# Actuators_Schematic.net
KiCad netlist of a schematic drawn in Altium Designer
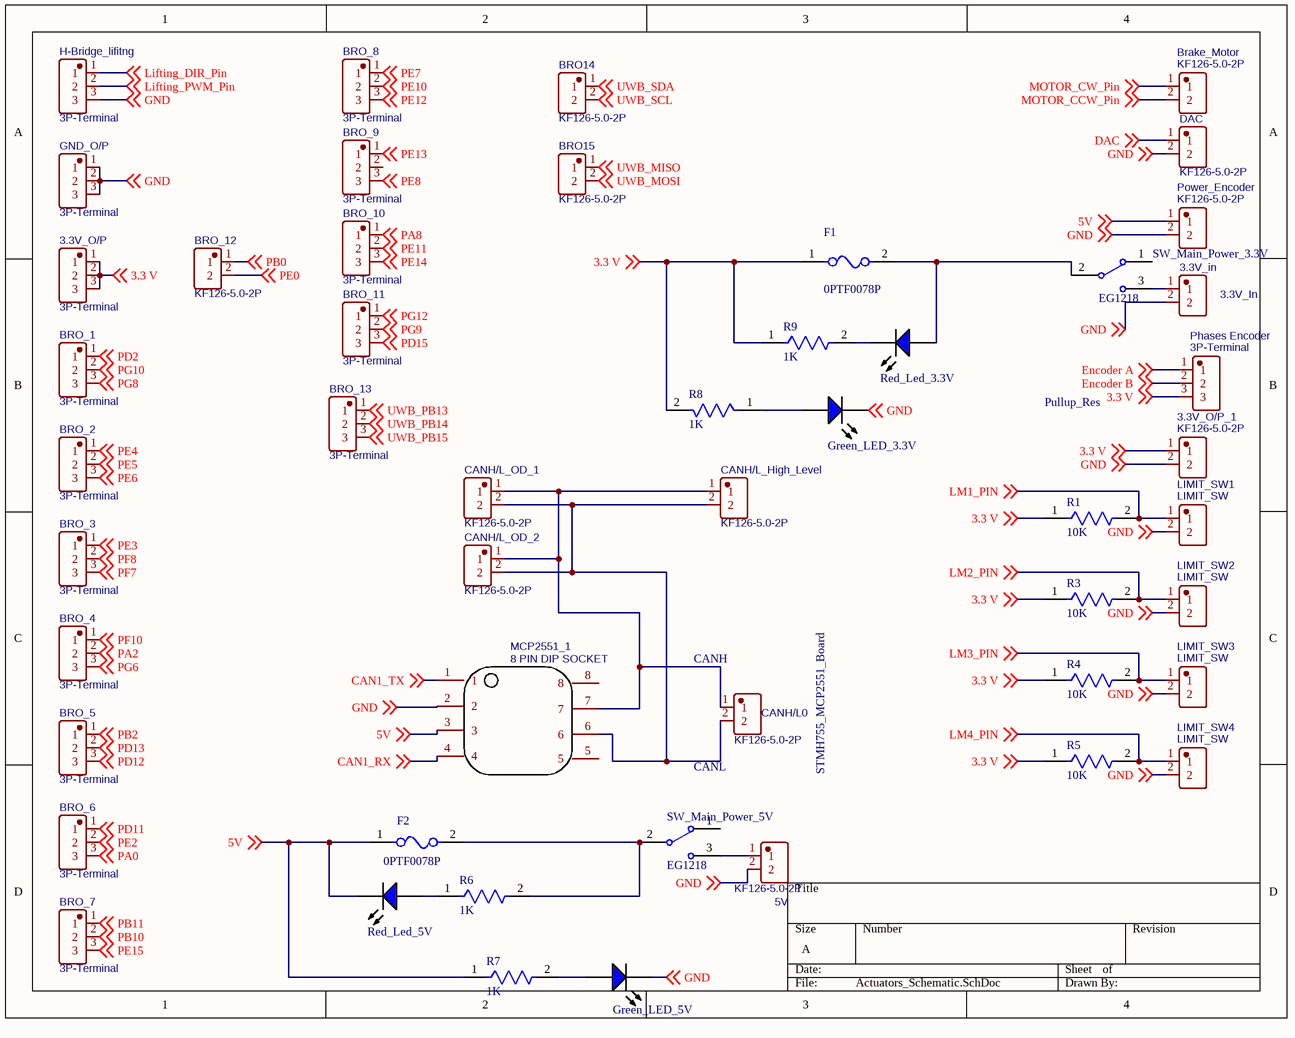
[diagram p0: Actuators_Schematic.SchDoc]

(export (version "E")
  (design (tool "Eeschema 10.0.6"))
  (components
    (comp (ref "3.3V_in")
      (value "3.3V_In")
      (footprint "CONN-TH_P5.00_KF126-5.0-2P")
      (fields
        (field (name "MANUFACTURER") "Cixi Kefa Elec")
        (field (name "MANUFACTURER PART") "KF126-5.0-2P")
        (field (name "CONTRIBUTOR") "LCSC")
      )
      (libsource (lib "altium-import") (part "root_0_KF126-5.0-2P_"))
    )
    (comp (ref "3.3V_O/P")
      (value "3P-Terminal")
      (footprint "CONN-TH_3P-P5.00_KF126-5.0-3P")
      (fields
        (field (name "MANUFACTURER") "Cixi Kefa Elec")
        (field (name "MANUFACTURER PART") "KF126-5.0-3P")
        (field (name "CONTRIBUTOR") "thulasikrishna")
      )
      (libsource (lib "altium-import") (part "root_0_mirrored_Limit Switch_"))
    )
    (comp (ref "3.3V_O/P_1")
      (value "KF126-5.0-2P")
      (footprint "CONN-TH_P5.00_KF126-5.0-2P")
      (fields (field (name "MANUFACTURER") "Cixi Kefa Elec") (field (name "CONTRIBUTOR") "LCSC"))
      (libsource (lib "altium-import") (part "root_0_KF126-5.0-2P_"))
    )
    (comp (ref "5V")
      (value "KF126-5.0-2P")
      (footprint "CONN-TH_P5.00_KF126-5.0-2P")
      (fields (field (name "MANUFACTURER") "Cixi Kefa Elec") (field (name "CONTRIBUTOR") "LCSC"))
      (libsource (lib "altium-import") (part "root_0_KF126-5.0-2P_"))
    )
    (comp (ref "Brake_Motor")
      (value "KF126-5.0-2P")
      (footprint "CONN-TH_P5.00_KF126-5.0-2P")
      (fields (field (name "MANUFACTURER") "Cixi Kefa Elec") (field (name "CONTRIBUTOR") "LCSC"))
      (libsource (lib "altium-import") (part "root_0_KF126-5.0-2P_"))
    )
    (comp (ref "BRO14")
      (value "KF126-5.0-2P")
      (footprint "CONN-TH_P5.00_KF126-5.0-2P")
      (fields (field (name "MANUFACTURER") "Cixi Kefa Elec") (field (name "CONTRIBUTOR") "LCSC"))
      (libsource (lib "altium-import") (part "root_0_mirrored_KF126-5.0-2P_"))
    )
    (comp (ref "BRO15")
      (value "KF126-5.0-2P")
      (footprint "CONN-TH_P5.00_KF126-5.0-2P")
      (fields (field (name "MANUFACTURER") "Cixi Kefa Elec") (field (name "CONTRIBUTOR") "LCSC"))
      (libsource (lib "altium-import") (part "root_0_mirrored_KF126-5.0-2P_"))
    )
    (comp (ref "BRO_1")
      (value "3P-Terminal")
      (footprint "CONN-TH_3P-P5.00_KF126-5.0-3P")
      (fields
        (field (name "MANUFACTURER") "Cixi Kefa Elec")
        (field (name "MANUFACTURER PART") "KF126-5.0-3P")
        (field (name "CONTRIBUTOR") "thulasikrishna")
      )
      (libsource (lib "altium-import") (part "root_0_mirrored_Limit Switch_"))
    )
    (comp (ref "BRO_2")
      (value "3P-Terminal")
      (footprint "CONN-TH_3P-P5.00_KF126-5.0-3P")
      (fields
        (field (name "MANUFACTURER") "Cixi Kefa Elec")
        (field (name "MANUFACTURER PART") "KF126-5.0-3P")
        (field (name "CONTRIBUTOR") "thulasikrishna")
      )
      (libsource (lib "altium-import") (part "root_0_mirrored_Limit Switch_"))
    )
    (comp (ref "BRO_3")
      (value "3P-Terminal")
      (footprint "CONN-TH_3P-P5.00_KF126-5.0-3P")
      (fields
        (field (name "MANUFACTURER") "Cixi Kefa Elec")
        (field (name "MANUFACTURER PART") "KF126-5.0-3P")
        (field (name "CONTRIBUTOR") "thulasikrishna")
      )
      (libsource (lib "altium-import") (part "root_0_mirrored_Limit Switch_"))
    )
    (comp (ref "BRO_4")
      (value "3P-Terminal")
      (footprint "CONN-TH_3P-P5.00_KF126-5.0-3P")
      (fields
        (field (name "MANUFACTURER") "Cixi Kefa Elec")
        (field (name "MANUFACTURER PART") "KF126-5.0-3P")
        (field (name "CONTRIBUTOR") "thulasikrishna")
      )
      (libsource (lib "altium-import") (part "root_0_mirrored_Limit Switch_"))
    )
    (comp (ref "BRO_5")
      (value "3P-Terminal")
      (footprint "CONN-TH_3P-P5.00_KF126-5.0-3P")
      (fields
        (field (name "MANUFACTURER") "Cixi Kefa Elec")
        (field (name "MANUFACTURER PART") "KF126-5.0-3P")
        (field (name "CONTRIBUTOR") "thulasikrishna")
      )
      (libsource (lib "altium-import") (part "root_0_mirrored_Limit Switch_"))
    )
    (comp (ref "BRO_6")
      (value "3P-Terminal")
      (footprint "CONN-TH_3P-P5.00_KF126-5.0-3P")
      (fields
        (field (name "MANUFACTURER") "Cixi Kefa Elec")
        (field (name "MANUFACTURER PART") "KF126-5.0-3P")
        (field (name "CONTRIBUTOR") "thulasikrishna")
      )
      (libsource (lib "altium-import") (part "root_0_mirrored_Limit Switch_"))
    )
    (comp (ref "BRO_7")
      (value "3P-Terminal")
      (footprint "CONN-TH_3P-P5.00_KF126-5.0-3P")
      (fields
        (field (name "MANUFACTURER") "Cixi Kefa Elec")
        (field (name "MANUFACTURER PART") "KF126-5.0-3P")
        (field (name "CONTRIBUTOR") "thulasikrishna")
      )
      (libsource (lib "altium-import") (part "root_0_mirrored_Limit Switch_"))
    )
    (comp (ref "BRO_8")
      (value "3P-Terminal")
      (footprint "CONN-TH_3P-P5.00_KF126-5.0-3P")
      (fields
        (field (name "MANUFACTURER") "Cixi Kefa Elec")
        (field (name "MANUFACTURER PART") "KF126-5.0-3P")
        (field (name "CONTRIBUTOR") "thulasikrishna")
      )
      (libsource (lib "altium-import") (part "root_0_mirrored_Limit Switch_"))
    )
    (comp (ref "BRO_9")
      (value "3P-Terminal")
      (footprint "CONN-TH_3P-P5.00_KF126-5.0-3P")
      (fields
        (field (name "MANUFACTURER") "Cixi Kefa Elec")
        (field (name "MANUFACTURER PART") "KF126-5.0-3P")
        (field (name "CONTRIBUTOR") "thulasikrishna")
      )
      (libsource (lib "altium-import") (part "root_0_mirrored_Limit Switch_"))
    )
    (comp (ref "BRO_10")
      (value "3P-Terminal")
      (footprint "CONN-TH_3P-P5.00_KF126-5.0-3P")
      (fields
        (field (name "MANUFACTURER") "Cixi Kefa Elec")
        (field (name "MANUFACTURER PART") "KF126-5.0-3P")
        (field (name "CONTRIBUTOR") "thulasikrishna")
      )
      (libsource (lib "altium-import") (part "root_0_mirrored_Limit Switch_"))
    )
    (comp (ref "BRO_11")
      (value "3P-Terminal")
      (footprint "CONN-TH_3P-P5.00_KF126-5.0-3P")
      (fields
        (field (name "MANUFACTURER") "Cixi Kefa Elec")
        (field (name "MANUFACTURER PART") "KF126-5.0-3P")
        (field (name "CONTRIBUTOR") "thulasikrishna")
      )
      (libsource (lib "altium-import") (part "root_0_mirrored_Limit Switch_"))
    )
    (comp (ref "BRO_12")
      (value "KF126-5.0-2P")
      (footprint "CONN-TH_P5.00_KF126-5.0-2P")
      (fields (field (name "MANUFACTURER") "Cixi Kefa Elec") (field (name "CONTRIBUTOR") "LCSC"))
      (libsource (lib "altium-import") (part "root_0_mirrored_KF126-5.0-2P_"))
    )
    (comp (ref "BRO_13")
      (value "3P-Terminal")
      (footprint "CONN-TH_3P-P5.00_KF126-5.0-3P")
      (fields
        (field (name "MANUFACTURER") "Cixi Kefa Elec")
        (field (name "MANUFACTURER PART") "KF126-5.0-3P")
        (field (name "CONTRIBUTOR") "thulasikrishna")
      )
      (libsource (lib "altium-import") (part "root_0_mirrored_Limit Switch_"))
    )
    (comp (ref "CANH/L0")
      (value "KF126-5.0-2P")
      (footprint "CONN-TH_P5.00_KF126-5.0-2P")
      (fields (field (name "MANUFACTURER") "Cixi Kefa Elec") (field (name "CONTRIBUTOR") "LCSC"))
      (libsource (lib "altium-import") (part "root_0_KF126-5.0-2P_"))
    )
    (comp (ref "CANH/L_High_Level")
      (value "KF126-5.0-2P")
      (footprint "CONN-TH_P5.00_KF126-5.0-2P")
      (fields (field (name "MANUFACTURER") "Cixi Kefa Elec") (field (name "CONTRIBUTOR") "LCSC"))
      (libsource (lib "altium-import") (part "root_0_KF126-5.0-2P_"))
    )
    (comp (ref "CANH/L_OD_1")
      (value "KF126-5.0-2P")
      (footprint "CONN-TH_P5.00_KF126-5.0-2P")
      (fields (field (name "MANUFACTURER") "Cixi Kefa Elec") (field (name "CONTRIBUTOR") "LCSC"))
      (libsource (lib "altium-import") (part "root_0_mirrored_KF126-5.0-2P_"))
    )
    (comp (ref "CANH/L_OD_2")
      (value "KF126-5.0-2P")
      (footprint "CONN-TH_P5.00_KF126-5.0-2P")
      (fields (field (name "MANUFACTURER") "Cixi Kefa Elec") (field (name "CONTRIBUTOR") "LCSC"))
      (libsource (lib "altium-import") (part "root_0_mirrored_KF126-5.0-2P_"))
    )
    (comp (ref "DAC")
      (value "KF126-5.0-2P")
      (footprint "CONN-TH_P5.00_KF126-5.0-2P")
      (fields (field (name "MANUFACTURER") "Cixi Kefa Elec") (field (name "CONTRIBUTOR") "LCSC"))
      (libsource (lib "altium-import") (part "root_0_KF126-5.0-2P_"))
    )
    (comp (ref "F1")
      (value "0PTF0078P")
      (footprint "FP-0PTF0078P-MFG")
      (description "FUSE BLOCK CARTRIDGE PCB")
      (fields
        (field (name "OCTOPART") "https://octopart.com/0ptf0078p-littelfuse-13255855")
        (field (name "MANUFACTURER") "Littelfuse Inc")
      )
      (libsource (lib "Altium Content Vault") (part "5bcf9b9f640e542cf0359d10258e979"))
    )
    (comp (ref "F2")
      (value "0PTF0078P")
      (footprint "FP-0PTF0078P-MFG")
      (description "FUSE BLOCK CARTRIDGE PCB")
      (fields
        (field (name "OCTOPART") "https://octopart.com/0ptf0078p-littelfuse-13255855")
        (field (name "MANUFACTURER") "Littelfuse Inc")
      )
      (libsource (lib "Altium Content Vault") (part "5bcf9b9f640e542cf0359d10258e979"))
    )
    (comp (ref "GND_O/P")
      (value "3P-Terminal")
      (footprint "CONN-TH_3P-P5.00_KF126-5.0-3P")
      (fields
        (field (name "MANUFACTURER") "Cixi Kefa Elec")
        (field (name "MANUFACTURER PART") "KF126-5.0-3P")
        (field (name "CONTRIBUTOR") "thulasikrishna")
      )
      (libsource (lib "altium-import") (part "root_0_mirrored_Limit Switch_"))
    )
    (comp (ref "Green_LED_3.3V")
      (value "WP710A10QBC/D")
      (footprint "KING-WP710A10QBCD_V")
      (description "Blue LED, 3.3 V, 20 mA, -40 to 85 degC, 2-Pin THD, RoHS, Bulk")
      (fields (field (name "MANUFACTURER") "Kingbright"))
      (libsource (lib "Altium Content Vault") (part "LED-BLUE-AK-2"))
    )
    (comp (ref "Green_LED_5V")
      (value "WP710A10QBC/D")
      (footprint "KING-WP710A10QBCD_V")
      (description "Blue LED, 3.3 V, 20 mA, -40 to 85 degC, 2-Pin THD, RoHS, Bulk")
      (fields (field (name "MANUFACTURER") "Kingbright"))
      (libsource (lib "Altium Content Vault") (part "LED-BLUE-AK-2"))
    )
    (comp (ref "H-Bridge_lifitng")
      (value "3P-Terminal")
      (footprint "CONN-TH_3P-P5.00_KF126-5.0-3P")
      (fields
        (field (name "MANUFACTURER") "Cixi Kefa Elec")
        (field (name "MANUFACTURER PART") "KF126-5.0-3P")
        (field (name "CONTRIBUTOR") "thulasikrishna")
      )
      (libsource (lib "altium-import") (part "root_0_mirrored_Limit Switch_"))
    )
    (comp (ref "LIMIT_SW1")
      (value "LIMIT_SW")
      (footprint "CONN-TH_P5.00_KF126-5.0-2P")
      (fields
        (field (name "MANUFACTURER") "Cixi Kefa Elec")
        (field (name "MANUFACTURER PART") "KF126-5.0-2P")
        (field (name "CONTRIBUTOR") "LCSC")
      )
      (libsource (lib "altium-import") (part "root_0_KF126-5.0-2P_"))
    )
    (comp (ref "LIMIT_SW2")
      (value "LIMIT_SW")
      (footprint "CONN-TH_P5.00_KF126-5.0-2P")
      (fields
        (field (name "MANUFACTURER") "Cixi Kefa Elec")
        (field (name "MANUFACTURER PART") "KF126-5.0-2P")
        (field (name "CONTRIBUTOR") "LCSC")
      )
      (libsource (lib "altium-import") (part "root_0_KF126-5.0-2P_"))
    )
    (comp (ref "LIMIT_SW3")
      (value "LIMIT_SW")
      (footprint "CONN-TH_P5.00_KF126-5.0-2P")
      (fields
        (field (name "MANUFACTURER") "Cixi Kefa Elec")
        (field (name "MANUFACTURER PART") "KF126-5.0-2P")
        (field (name "CONTRIBUTOR") "LCSC")
      )
      (libsource (lib "altium-import") (part "root_0_KF126-5.0-2P_"))
    )
    (comp (ref "LIMIT_SW4")
      (value "LIMIT_SW")
      (footprint "CONN-TH_P5.00_KF126-5.0-2P")
      (fields
        (field (name "MANUFACTURER") "Cixi Kefa Elec")
        (field (name "MANUFACTURER PART") "KF126-5.0-2P")
        (field (name "CONTRIBUTOR") "LCSC")
      )
      (libsource (lib "altium-import") (part "root_0_KF126-5.0-2P_"))
    )
    (comp (ref "MCP2551_1")
      (value "8 PIN DIP SOCKET")
      (footprint "DIP 8 PIN SOCKET")
      (fields (field (name "CONTRIBUTOR") "uniqengineeringworks"))
      (libsource (lib "altium-import") (part "root_0_8 PIN DIP SOCKET_"))
    )
    (comp (ref "Phases Encoder")
      (value "3P-Terminal")
      (footprint "CONN-TH_3P-P5.00_KF126-5.0-3P")
      (fields
        (field (name "MANUFACTURER") "Cixi Kefa Elec")
        (field (name "MANUFACTURER PART") "KF126-5.0-3P")
        (field (name "CONTRIBUTOR") "thulasikrishna")
      )
      (libsource (lib "altium-import") (part "root_0_Limit Switch_"))
    )
    (comp (ref "Power_Encoder")
      (value "KF126-5.0-2P")
      (footprint "CONN-TH_P5.00_KF126-5.0-2P")
      (fields (field (name "MANUFACTURER") "Cixi Kefa Elec") (field (name "CONTRIBUTOR") "LCSC"))
      (libsource (lib "altium-import") (part "root_0_KF126-5.0-2P_"))
    )
    (comp (ref "R1")
      (value "10K")
      (footprint "FP-MFR-12-MFG")
      (description "RES MF 1/6W 1% AXIAL")
      (fields (field (name "TOLERANCE") "1%"))
      (libsource (lib "Altium Content Vault") (part "1029c3af85768c4190bb7ad29bc67b5"))
    )
    (comp (ref "R3")
      (value "10K")
      (footprint "FP-MFR-12-MFG")
      (description "RES MF 1/6W 1% AXIAL")
      (fields (field (name "TOLERANCE") "1%"))
      (libsource (lib "Altium Content Vault") (part "1029c3af85768c4190bb7ad29bc67b5"))
    )
    (comp (ref "R4")
      (value "10K")
      (footprint "FP-MFR-12-MFG")
      (description "RES MF 1/6W 1% AXIAL")
      (fields (field (name "TOLERANCE") "1%"))
      (libsource (lib "Altium Content Vault") (part "1029c3af85768c4190bb7ad29bc67b5"))
    )
    (comp (ref "R5")
      (value "10K")
      (footprint "FP-MFR-12-MFG")
      (description "RES MF 1/6W 1% AXIAL")
      (fields (field (name "TOLERANCE") "1%"))
      (libsource (lib "Altium Content Vault") (part "1029c3af85768c4190bb7ad29bc67b5"))
    )
    (comp (ref "R6")
      (value "1K")
      (footprint "FP-MFR-12-MFG")
      (description "RES MF 1/6W 1% AXIAL")
      (fields (field (name "TOLERANCE") "1%"))
      (libsource (lib "Altium Content Vault") (part "1029c3af85768c4190bb7ad29bc67b5"))
    )
    (comp (ref "R7")
      (value "1K")
      (footprint "FP-MFR-12-MFG")
      (description "RES MF 1/6W 1% AXIAL")
      (fields (field (name "TOLERANCE") "1%"))
      (libsource (lib "Altium Content Vault") (part "1029c3af85768c4190bb7ad29bc67b5"))
    )
    (comp (ref "R8")
      (value "1K")
      (footprint "FP-MFR-12-MFG")
      (description "RES MF 1/6W 1% AXIAL")
      (fields (field (name "TOLERANCE") "1%"))
      (libsource (lib "Altium Content Vault") (part "1029c3af85768c4190bb7ad29bc67b5"))
    )
    (comp (ref "R9")
      (value "1K")
      (footprint "FP-MFR-12-MFG")
      (description "RES MF 1/6W 1% AXIAL")
      (fields (field (name "TOLERANCE") "1%"))
      (libsource (lib "Altium Content Vault") (part "1029c3af85768c4190bb7ad29bc67b5"))
    )
    (comp (ref "Red_Led_3.3V")
      (value "WP710A10QBC/D")
      (footprint "KING-WP710A10QBCD_V")
      (description "Blue LED, 3.3 V, 20 mA, -40 to 85 degC, 2-Pin THD, RoHS, Bulk")
      (fields (field (name "MANUFACTURER") "Kingbright"))
      (libsource (lib "Altium Content Vault") (part "LED-BLUE-AK-2"))
    )
    (comp (ref "Red_Led_5V")
      (value "WP710A10QBC/D")
      (footprint "KING-WP710A10QBCD_V")
      (description "Blue LED, 3.3 V, 20 mA, -40 to 85 degC, 2-Pin THD, RoHS, Bulk")
      (fields (field (name "MANUFACTURER") "Kingbright"))
      (libsource (lib "Altium Content Vault") (part "LED-BLUE-AK-2"))
    )
    (comp (ref "SW_Main_Power_3.3V")
      (value "EG1218")
      (footprint "ESWI-EG1218_V")
      (description "Slide Switch, 500 V, -20 to 70 degC, 3-Pin THD, RoHS")
      (libsource (lib "Altium Content Vault") (part "SW-SPDT-3_B"))
    )
    (comp (ref "SW_Main_Power_5V")
      (value "EG1218")
      (footprint "ESWI-EG1218_V")
      (description "Slide Switch, 500 V, -20 to 70 degC, 3-Pin THD, RoHS")
      (libsource (lib "Altium Content Vault") (part "SW-SPDT-3_B"))
    )
  )
  (nets
    (net (code "1") (name "3.3 V") (class "Default")
      (node (ref "3.3V_O/P") (pin "1") (pinfunction "1_1") (pintype "passive"))
      (node (ref "3.3V_O/P") (pin "2") (pinfunction "2_2") (pintype "passive"))
      (node (ref "3.3V_O/P") (pin "3") (pinfunction "3_3") (pintype "passive"))
      (node (ref "3.3V_O/P_1") (pin "1") (pinfunction "1_1") (pintype "passive"))
      (node (ref "F1") (pin "1") (pinfunction "1_1") (pintype "passive"))
      (node (ref "Phases Encoder") (pin "3") (pinfunction "3_3") (pintype "passive"))
      (node (ref "R1") (pin "1") (pinfunction "1_1") (pintype "passive"))
      (node (ref "R3") (pin "1") (pinfunction "1_1") (pintype "passive"))
      (node (ref "R4") (pin "1") (pinfunction "1_1") (pintype "passive"))
      (node (ref "R5") (pin "1") (pinfunction "1_1") (pintype "passive"))
      (node (ref "R8") (pin "2") (pinfunction "2_2") (pintype "passive"))
      (node (ref "R9") (pin "1") (pinfunction "1_1") (pintype "passive"))
    )
    (net (code "2") (name "5V") (class "Default")
      (node (ref "F2") (pin "1") (pinfunction "1_1") (pintype "passive"))
      (node (ref "MCP2551_1") (pin "3") (pinfunction "3_3") (pintype "passive"))
      (node (ref "Power_Encoder") (pin "1") (pinfunction "1_1") (pintype "passive"))
      (node (ref "R7") (pin "1") (pinfunction "1_1") (pintype "passive"))
      (node (ref "Red_Led_5V") (pin "2") (pinfunction "K_2") (pintype "passive"))
    )
    (net (code "3") (name "CAN1_RX") (class "Default")
      (node (ref "MCP2551_1") (pin "4") (pinfunction "4_4") (pintype "passive"))
    )
    (net (code "4") (name "CAN1_TX") (class "Default")
      (node (ref "MCP2551_1") (pin "1") (pinfunction "1_1") (pintype "passive"))
    )
    (net (code "5") (name "DAC") (class "Default")
      (node (ref "DAC") (pin "1") (pinfunction "1_1") (pintype "passive"))
    )
    (net (code "6") (name "Encoder A") (class "Default")
      (node (ref "Phases Encoder") (pin "1") (pinfunction "1_1") (pintype "passive"))
    )
    (net (code "7") (name "Encoder B") (class "Default")
      (node (ref "Phases Encoder") (pin "2") (pinfunction "2_2") (pintype "passive"))
    )
    (net (code "8") (name "GND") (class "Default")
      (node (ref "3.3V_O/P_1") (pin "2") (pinfunction "2_2") (pintype "passive"))
      (node (ref "3.3V_in") (pin "2") (pinfunction "2_2") (pintype "passive"))
      (node (ref "5V") (pin "2") (pinfunction "2_2") (pintype "passive"))
      (node (ref "DAC") (pin "2") (pinfunction "2_2") (pintype "passive"))
      (node (ref "GND_O/P") (pin "1") (pinfunction "1_1") (pintype "passive"))
      (node (ref "GND_O/P") (pin "2") (pinfunction "2_2") (pintype "passive"))
      (node (ref "GND_O/P") (pin "3") (pinfunction "3_3") (pintype "passive"))
      (node (ref "Green_LED_3.3V") (pin "2") (pinfunction "K_2") (pintype "passive"))
      (node (ref "Green_LED_5V") (pin "2") (pinfunction "K_2") (pintype "passive"))
      (node (ref "H-Bridge_lifitng") (pin "3") (pinfunction "3_3") (pintype "passive"))
      (node (ref "LIMIT_SW1") (pin "2") (pinfunction "2_2") (pintype "passive"))
      (node (ref "LIMIT_SW2") (pin "2") (pinfunction "2_2") (pintype "passive"))
      (node (ref "LIMIT_SW3") (pin "2") (pinfunction "2_2") (pintype "passive"))
      (node (ref "LIMIT_SW4") (pin "2") (pinfunction "2_2") (pintype "passive"))
      (node (ref "MCP2551_1") (pin "2") (pinfunction "2_2") (pintype "passive"))
      (node (ref "Power_Encoder") (pin "2") (pinfunction "2_2") (pintype "passive"))
    )
    (net (code "9") (name "LM1_PIN") (class "Default")
      (node (ref "LIMIT_SW1") (pin "1") (pinfunction "1_1") (pintype "passive"))
      (node (ref "R1") (pin "2") (pinfunction "2_2") (pintype "passive"))
    )
    (net (code "10") (name "LM2_PIN") (class "Default")
      (node (ref "LIMIT_SW2") (pin "1") (pinfunction "1_1") (pintype "passive"))
      (node (ref "R3") (pin "2") (pinfunction "2_2") (pintype "passive"))
    )
    (net (code "11") (name "LM3_PIN") (class "Default")
      (node (ref "LIMIT_SW3") (pin "1") (pinfunction "1_1") (pintype "passive"))
      (node (ref "R4") (pin "2") (pinfunction "2_2") (pintype "passive"))
    )
    (net (code "12") (name "LM4_PIN") (class "Default")
      (node (ref "LIMIT_SW4") (pin "1") (pinfunction "1_1") (pintype "passive"))
      (node (ref "R5") (pin "2") (pinfunction "2_2") (pintype "passive"))
    )
    (net (code "13") (name "Lifting_DIR_Pin") (class "Default")
      (node (ref "H-Bridge_lifitng") (pin "1") (pinfunction "1_1") (pintype "passive"))
    )
    (net (code "14") (name "Lifting_PWM_Pin") (class "Default")
      (node (ref "H-Bridge_lifitng") (pin "2") (pinfunction "2_2") (pintype "passive"))
    )
    (net (code "15") (name "MOTOR_CCW_Pin") (class "Default")
      (node (ref "Brake_Motor") (pin "2") (pinfunction "2_2") (pintype "passive"))
    )
    (net (code "16") (name "MOTOR_CW_Pin") (class "Default")
      (node (ref "Brake_Motor") (pin "1") (pinfunction "1_1") (pintype "passive"))
    )
    (net (code "17") (name "Net-(3.3V_in-Pad1)") (class "Default")
      (node (ref "3.3V_in") (pin "1") (pinfunction "1_1") (pintype "passive"))
      (node (ref "SW_Main_Power_3.3V") (pin "3") (pinfunction "3_3") (pintype "passive"))
    )
    (net (code "18") (name "Net-(5V-Pad1)") (class "Default")
      (node (ref "5V") (pin "1") (pinfunction "1_1") (pintype "passive"))
      (node (ref "SW_Main_Power_5V") (pin "3") (pinfunction "3_3") (pintype "passive"))
    )
    (net (code "19") (name "Net-(CANH/L0-Pad1)") (class "Default")
      (node (ref "CANH/L0") (pin "1") (pinfunction "1_1") (pintype "passive"))
      (node (ref "CANH/L_High_Level") (pin "1") (pinfunction "1_1") (pintype "passive"))
      (node (ref "CANH/L_OD_1") (pin "1") (pinfunction "1_1") (pintype "passive"))
      (node (ref "CANH/L_OD_2") (pin "1") (pinfunction "1_1") (pintype "passive"))
      (node (ref "MCP2551_1") (pin "7") (pinfunction "7_7") (pintype "passive"))
    )
    (net (code "20") (name "Net-(CANH/L0-Pad2)") (class "Default")
      (node (ref "CANH/L0") (pin "2") (pinfunction "2_2") (pintype "passive"))
      (node (ref "CANH/L_High_Level") (pin "2") (pinfunction "2_2") (pintype "passive"))
      (node (ref "CANH/L_OD_1") (pin "2") (pinfunction "2_2") (pintype "passive"))
      (node (ref "CANH/L_OD_2") (pin "2") (pinfunction "2_2") (pintype "passive"))
      (node (ref "MCP2551_1") (pin "6") (pinfunction "6_6") (pintype "passive"))
    )
    (net (code "21") (name "Net-(Green_LED_3.3V-A)") (class "Default")
      (node (ref "Green_LED_3.3V") (pin "1") (pinfunction "A_1") (pintype "passive"))
      (node (ref "R8") (pin "1") (pinfunction "1_1") (pintype "passive"))
    )
    (net (code "22") (name "Net-(Green_LED_5V-A)") (class "Default")
      (node (ref "Green_LED_5V") (pin "1") (pinfunction "A_1") (pintype "passive"))
      (node (ref "R7") (pin "2") (pinfunction "2_2") (pintype "passive"))
    )
    (net (code "23") (name "Net-(Red_Led_3.3V-A)") (class "Default")
      (node (ref "F1") (pin "2") (pinfunction "2_2") (pintype "passive"))
      (node (ref "Red_Led_3.3V") (pin "1") (pinfunction "A_1") (pintype "passive"))
      (node (ref "SW_Main_Power_3.3V") (pin "2") (pinfunction "COM_2") (pintype "passive"))
    )
    (net (code "24") (name "Net-(Red_Led_3.3V-K)") (class "Default")
      (node (ref "R9") (pin "2") (pinfunction "2_2") (pintype "passive"))
      (node (ref "Red_Led_3.3V") (pin "2") (pinfunction "K_2") (pintype "passive"))
    )
    (net (code "25") (name "Net-(Red_Led_5V-A)") (class "Default")
      (node (ref "R6") (pin "1") (pinfunction "1_1") (pintype "passive"))
      (node (ref "Red_Led_5V") (pin "1") (pinfunction "A_1") (pintype "passive"))
    )
    (net (code "26") (name "Net-(SW_Main_Power_5V-COM)") (class "Default")
      (node (ref "F2") (pin "2") (pinfunction "2_2") (pintype "passive"))
      (node (ref "R6") (pin "2") (pinfunction "2_2") (pintype "passive"))
      (node (ref "SW_Main_Power_5V") (pin "2") (pinfunction "COM_2") (pintype "passive"))
    )
    (net (code "27") (name "PA0") (class "Default")
      (node (ref "BRO_6") (pin "3") (pinfunction "3_3") (pintype "passive"))
    )
    (net (code "28") (name "PA2") (class "Default")
      (node (ref "BRO_4") (pin "2") (pinfunction "2_2") (pintype "passive"))
    )
    (net (code "29") (name "PA8") (class "Default")
      (node (ref "BRO_10") (pin "1") (pinfunction "1_1") (pintype "passive"))
    )
    (net (code "30") (name "PB0") (class "Default")
      (node (ref "BRO_12") (pin "1") (pinfunction "1_1") (pintype "passive"))
    )
    (net (code "31") (name "PB2") (class "Default")
      (node (ref "BRO_5") (pin "1") (pinfunction "1_1") (pintype "passive"))
    )
    (net (code "32") (name "PB10") (class "Default")
      (node (ref "BRO_7") (pin "2") (pinfunction "2_2") (pintype "passive"))
    )
    (net (code "33") (name "PB11") (class "Default")
      (node (ref "BRO_7") (pin "1") (pinfunction "1_1") (pintype "passive"))
    )
    (net (code "34") (name "PD2") (class "Default")
      (node (ref "BRO_1") (pin "1") (pinfunction "1_1") (pintype "passive"))
    )
    (net (code "35") (name "PD11") (class "Default")
      (node (ref "BRO_6") (pin "1") (pinfunction "1_1") (pintype "passive"))
    )
    (net (code "36") (name "PD12") (class "Default")
      (node (ref "BRO_5") (pin "3") (pinfunction "3_3") (pintype "passive"))
    )
    (net (code "37") (name "PD13") (class "Default")
      (node (ref "BRO_5") (pin "2") (pinfunction "2_2") (pintype "passive"))
    )
    (net (code "38") (name "PD15") (class "Default")
      (node (ref "BRO_11") (pin "3") (pinfunction "3_3") (pintype "passive"))
    )
    (net (code "39") (name "PE0") (class "Default")
      (node (ref "BRO_12") (pin "2") (pinfunction "2_2") (pintype "passive"))
    )
    (net (code "40") (name "PE2") (class "Default")
      (node (ref "BRO_6") (pin "2") (pinfunction "2_2") (pintype "passive"))
    )
    (net (code "41") (name "PE3") (class "Default")
      (node (ref "BRO_3") (pin "1") (pinfunction "1_1") (pintype "passive"))
    )
    (net (code "42") (name "PE4") (class "Default")
      (node (ref "BRO_2") (pin "1") (pinfunction "1_1") (pintype "passive"))
    )
    (net (code "43") (name "PE5") (class "Default")
      (node (ref "BRO_2") (pin "2") (pinfunction "2_2") (pintype "passive"))
    )
    (net (code "44") (name "PE6") (class "Default")
      (node (ref "BRO_2") (pin "3") (pinfunction "3_3") (pintype "passive"))
    )
    (net (code "45") (name "PE7") (class "Default")
      (node (ref "BRO_8") (pin "1") (pinfunction "1_1") (pintype "passive"))
    )
    (net (code "46") (name "PE8") (class "Default")
      (node (ref "BRO_9") (pin "3") (pinfunction "3_3") (pintype "passive"))
    )
    (net (code "47") (name "PE10") (class "Default")
      (node (ref "BRO_8") (pin "2") (pinfunction "2_2") (pintype "passive"))
    )
    (net (code "48") (name "PE11") (class "Default")
      (node (ref "BRO_10") (pin "2") (pinfunction "2_2") (pintype "passive"))
    )
    (net (code "49") (name "PE12") (class "Default")
      (node (ref "BRO_8") (pin "3") (pinfunction "3_3") (pintype "passive"))
    )
    (net (code "50") (name "PE13") (class "Default")
      (node (ref "BRO_9") (pin "1") (pinfunction "1_1") (pintype "passive"))
    )
    (net (code "51") (name "PE14") (class "Default")
      (node (ref "BRO_10") (pin "3") (pinfunction "3_3") (pintype "passive"))
    )
    (net (code "52") (name "PE15") (class "Default")
      (node (ref "BRO_7") (pin "3") (pinfunction "3_3") (pintype "passive"))
    )
    (net (code "53") (name "PF7") (class "Default")
      (node (ref "BRO_3") (pin "3") (pinfunction "3_3") (pintype "passive"))
    )
    (net (code "54") (name "PF8") (class "Default")
      (node (ref "BRO_3") (pin "2") (pinfunction "2_2") (pintype "passive"))
    )
    (net (code "55") (name "PF10") (class "Default")
      (node (ref "BRO_4") (pin "1") (pinfunction "1_1") (pintype "passive"))
    )
    (net (code "56") (name "PG6") (class "Default")
      (node (ref "BRO_4") (pin "3") (pinfunction "3_3") (pintype "passive"))
    )
    (net (code "57") (name "PG8") (class "Default")
      (node (ref "BRO_1") (pin "3") (pinfunction "3_3") (pintype "passive"))
    )
    (net (code "58") (name "PG9") (class "Default")
      (node (ref "BRO_11") (pin "2") (pinfunction "2_2") (pintype "passive"))
    )
    (net (code "59") (name "PG10") (class "Default")
      (node (ref "BRO_1") (pin "2") (pinfunction "2_2") (pintype "passive"))
    )
    (net (code "60") (name "PG12") (class "Default")
      (node (ref "BRO_11") (pin "1") (pinfunction "1_1") (pintype "passive"))
    )
    (net (code "61") (name "UWB_MISO") (class "Default")
      (node (ref "BRO15") (pin "1") (pinfunction "1_1") (pintype "passive"))
    )
    (net (code "62") (name "UWB_MOSI") (class "Default")
      (node (ref "BRO15") (pin "2") (pinfunction "2_2") (pintype "passive"))
    )
    (net (code "63") (name "UWB_PB13") (class "Default")
      (node (ref "BRO_13") (pin "1") (pinfunction "1_1") (pintype "passive"))
    )
    (net (code "64") (name "UWB_PB14") (class "Default")
      (node (ref "BRO_13") (pin "2") (pinfunction "2_2") (pintype "passive"))
    )
    (net (code "65") (name "UWB_PB15") (class "Default")
      (node (ref "BRO_13") (pin "3") (pinfunction "3_3") (pintype "passive"))
    )
    (net (code "66") (name "UWB_SCL") (class "Default")
      (node (ref "BRO14") (pin "2") (pinfunction "2_2") (pintype "passive"))
    )
    (net (code "67") (name "UWB_SDA") (class "Default")
      (node (ref "BRO14") (pin "1") (pinfunction "1_1") (pintype "passive"))
    )
    (net (code "68") (name "unconnected-(BRO_9-Pad2)") (class "Default")
      (node (ref "BRO_9") (pin "2") (pinfunction "2_2") (pintype "passive"))
    )
    (net (code "69") (name "unconnected-(MCP2551_1-Pad5)") (class "Default")
      (node (ref "MCP2551_1") (pin "5") (pinfunction "5_5") (pintype "passive"))
    )
    (net (code "70") (name "unconnected-(MCP2551_1-Pad8)") (class "Default")
      (node (ref "MCP2551_1") (pin "8") (pinfunction "8_8") (pintype "passive"))
    )
    (net (code "71") (name "unconnected-(SW_Main_Power_3.3V-Pad1)") (class "Default")
      (node (ref "SW_Main_Power_3.3V") (pin "1") (pinfunction "1_1") (pintype "passive"))
    )
    (net (code "72") (name "unconnected-(SW_Main_Power_5V-Pad1)") (class "Default")
      (node (ref "SW_Main_Power_5V") (pin "1") (pinfunction "1_1") (pintype "passive"))
    )
  )
)
